# Pi_grammer.net
KiCad netlist of a schematic drawn in EAGLE
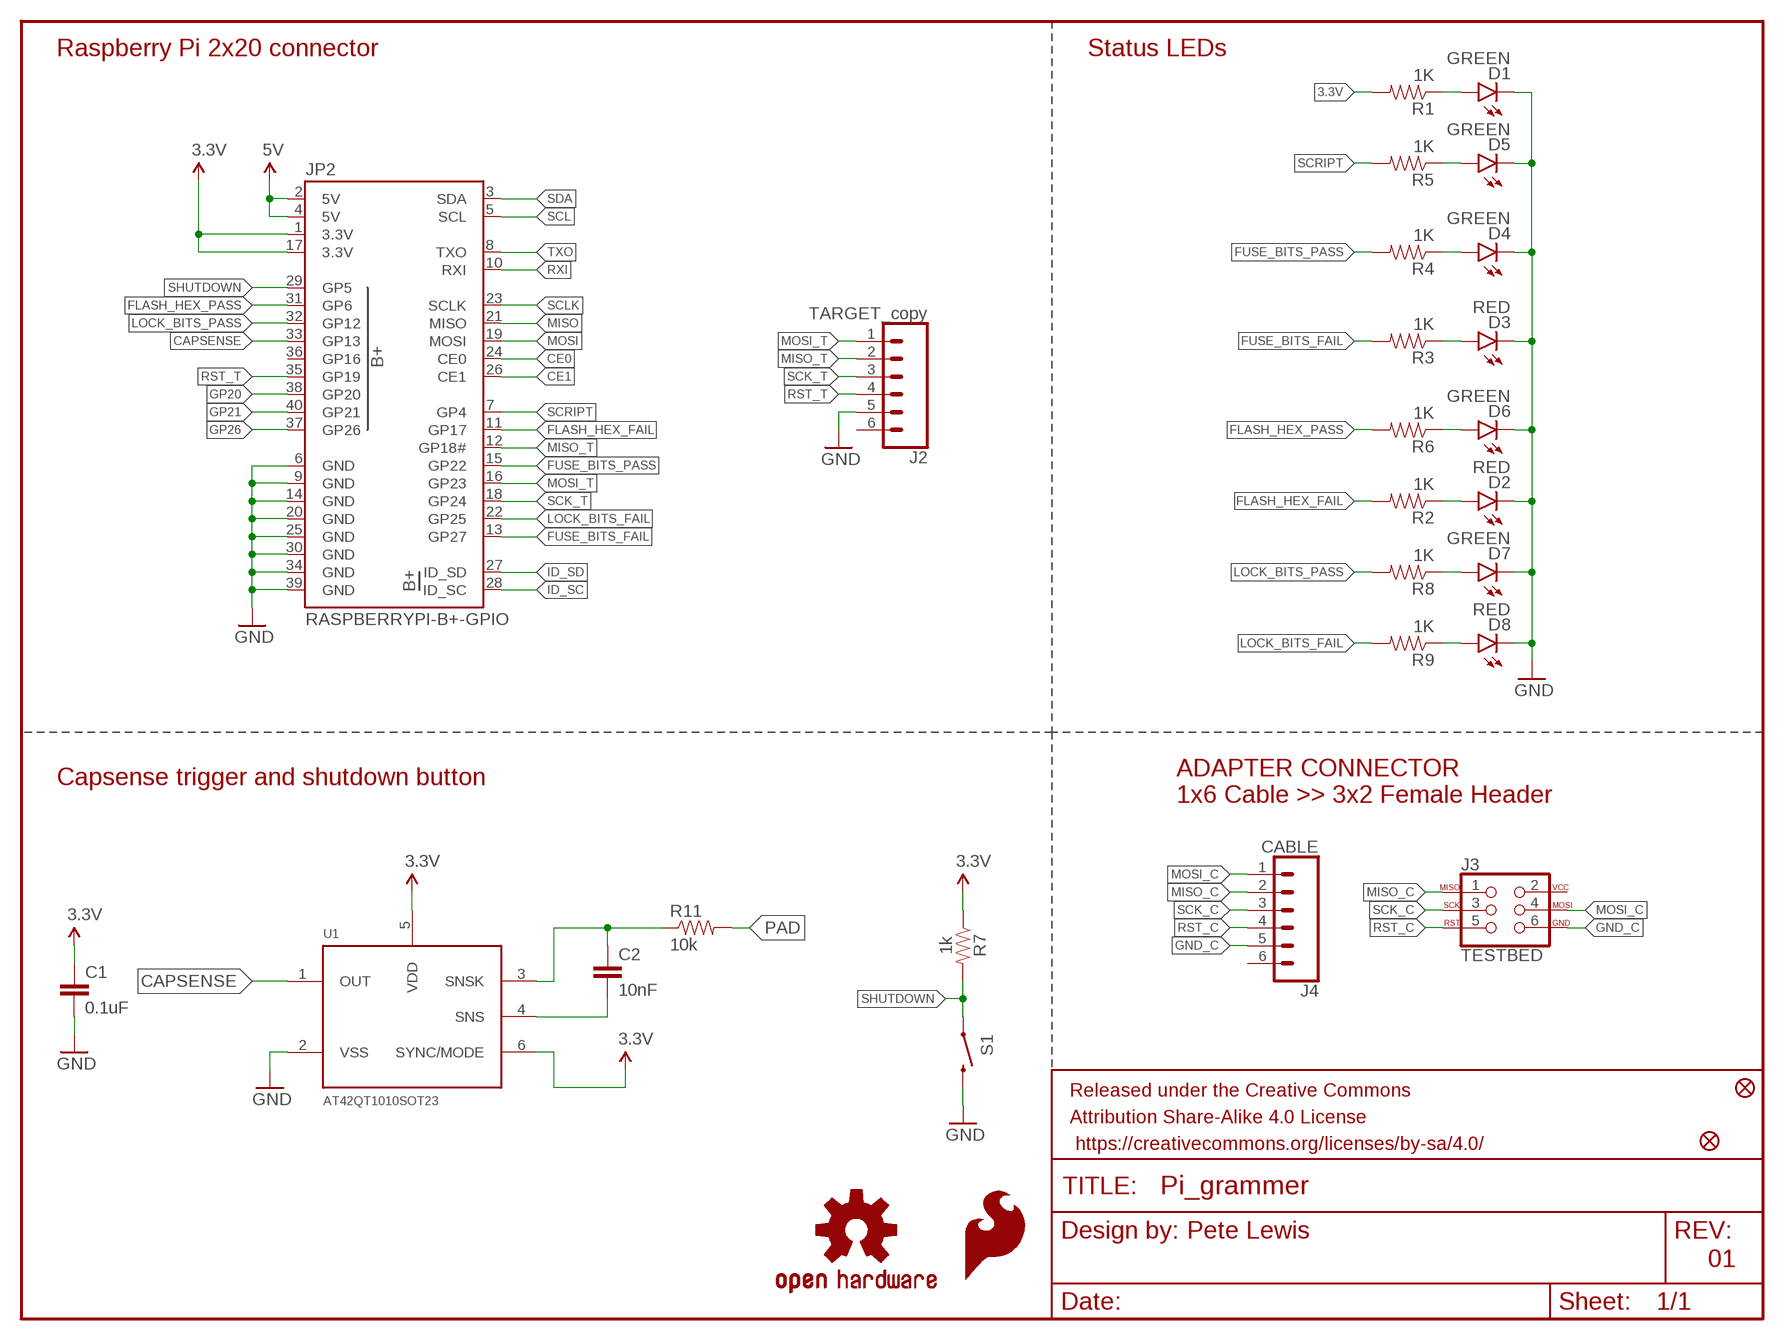
[diagram p0: schematic, sheet 1]

(export (version "E")
  (design (tool "Eeschema 10.0.6"))
  (components
    (comp (ref "C1")
      (value "0.1uF")
      (footprint "eagle-import:0603-CAP")
      (libsource (lib "eagle-import") (part "0.1UF-25V(+80/-20%)(0603)"))
    )
    (comp (ref "C2")
      (value "10nF")
      (footprint "eagle-import:0603-CAP")
      (libsource (lib "eagle-import") (part "10NF/10000PF-50V-10%(0603)"))
    )
    (comp (ref "D1")
      (value "GREEN")
      (footprint "eagle-import:LED-1206")
      (libsource (lib "eagle-import") (part "LED-GREEN1206"))
    )
    (comp (ref "D2")
      (value "RED")
      (footprint "eagle-import:LED-1206")
      (libsource (lib "eagle-import") (part "LED-RED1206"))
    )
    (comp (ref "D3")
      (value "RED")
      (footprint "eagle-import:LED-1206")
      (libsource (lib "eagle-import") (part "LED-RED1206"))
    )
    (comp (ref "D4")
      (value "GREEN")
      (footprint "eagle-import:LED-1206")
      (libsource (lib "eagle-import") (part "LED-GREEN1206"))
    )
    (comp (ref "D5")
      (value "GREEN")
      (footprint "eagle-import:LED-1206")
      (libsource (lib "eagle-import") (part "LED-GREEN1206"))
    )
    (comp (ref "D6")
      (value "GREEN")
      (footprint "eagle-import:LED-1206")
      (libsource (lib "eagle-import") (part "LED-GREEN1206"))
    )
    (comp (ref "D7")
      (value "GREEN")
      (footprint "eagle-import:LED-1206")
      (libsource (lib "eagle-import") (part "LED-GREEN1206"))
    )
    (comp (ref "D8")
      (value "RED")
      (footprint "eagle-import:LED-1206")
      (libsource (lib "eagle-import") (part "LED-RED1206"))
    )
    (comp (ref "FD1")
      (value "FIDUCIALUFIDUCIAL")
      (footprint "eagle-import:FIDUCIAL-MICRO")
      (libsource (lib "eagle-import") (part "FIDUCIALUFIDUCIAL"))
    )
    (comp (ref "FD2")
      (value "FIDUCIALUFIDUCIAL")
      (footprint "eagle-import:FIDUCIAL-MICRO")
      (libsource (lib "eagle-import") (part "FIDUCIALUFIDUCIAL"))
    )
    (comp (ref "FRAME1")
      (value "FRAME-LETTER")
      (footprint "eagle-import:CREATIVE_COMMONS")
      (libsource (lib "eagle-import") (part "FRAME-LETTER"))
    )
    (comp (ref "J2")
      (value "TARGET_copy")
      (footprint "eagle-import:MOLEX-1X6")
      (libsource (lib "eagle-import") (part "CONN_06POLAR"))
    )
    (comp (ref "J3")
      (value "TESTBED")
      (footprint "eagle-import:2X3_LOCK")
      (libsource (lib "eagle-import") (part "AVR_SPI_PROG_3X22X3_LOCK"))
    )
    (comp (ref "J4")
      (value "CABLE")
      (footprint "eagle-import:MOLEX-1X6-RA")
      (libsource (lib "eagle-import") (part "CONN_06RA"))
    )
    (comp (ref "JP2")
      (value "RASPBERRYPI-B+-GPIO")
      (footprint "eagle-import:2X20-SHROUDED")
      (libsource (lib "eagle-import") (part "RASPBERRYPI-B+-GPIO"))
    )
    (comp (ref "LOGO1")
      (value "SFE_LOGO_FLAME.1_INCH")
      (footprint "eagle-import:SFE_LOGO_FLAME_.1")
      (libsource (lib "eagle-import") (part "SFE_LOGO_FLAME.1_INCH"))
    )
    (comp (ref "LOGO2")
      (value "OSHW-LOGOS")
      (footprint "eagle-import:OSHW-LOGO-S")
      (libsource (lib "eagle-import") (part "OSHW-LOGOS"))
    )
    (comp (ref "R1")
      (value "1K")
      (footprint "eagle-import:0603-RES")
      (libsource (lib "eagle-import") (part "1KOHM-1/10W-1%(0603)"))
    )
    (comp (ref "R2")
      (value "1K")
      (footprint "eagle-import:0603-RES")
      (libsource (lib "eagle-import") (part "1KOHM-1/10W-1%(0603)"))
    )
    (comp (ref "R3")
      (value "1K")
      (footprint "eagle-import:0603-RES")
      (libsource (lib "eagle-import") (part "1KOHM-1/10W-1%(0603)"))
    )
    (comp (ref "R4")
      (value "1K")
      (footprint "eagle-import:0603-RES")
      (libsource (lib "eagle-import") (part "1KOHM-1/10W-1%(0603)"))
    )
    (comp (ref "R5")
      (value "1K")
      (footprint "eagle-import:0603-RES")
      (libsource (lib "eagle-import") (part "1KOHM-1/10W-1%(0603)"))
    )
    (comp (ref "R6")
      (value "1K")
      (footprint "eagle-import:0603-RES")
      (libsource (lib "eagle-import") (part "1KOHM-1/10W-1%(0603)"))
    )
    (comp (ref "R7")
      (value "1k")
      (footprint "eagle-import:0603")
      (libsource (lib "eagle-import") (part "1KOHM-0603-1/10W-1%"))
    )
    (comp (ref "R8")
      (value "1K")
      (footprint "eagle-import:0603-RES")
      (libsource (lib "eagle-import") (part "1KOHM-1/10W-1%(0603)"))
    )
    (comp (ref "R9")
      (value "1K")
      (footprint "eagle-import:0603-RES")
      (libsource (lib "eagle-import") (part "1KOHM-1/10W-1%(0603)"))
    )
    (comp (ref "R11")
      (value "10k")
      (footprint "eagle-import:0603-RES")
      (libsource (lib "eagle-import") (part "10KOHM-1/10W-1%(0603)0603"))
    )
    (comp (ref "S1")
      (value "SWITCH-MOMENTARY-2SMD")
      (footprint "eagle-import:TACTILE-SWITCH-SMD")
      (libsource (lib "eagle-import") (part "SWITCH-MOMENTARY-2SMD"))
    )
    (comp (ref "U1")
      (value "AT42QT1010SOT23")
      (footprint "eagle-import:SOT23-6")
      (libsource (lib "eagle-import") (part "AT42QT1010SOT23"))
    )
  )
  (nets
    (net (code "1") (name "3.3V") (class "Default")
      (node (ref "C1") (pin "1") (pinfunction "1_1") (pintype "passive"))
      (node (ref "JP2") (pin "1") (pinfunction "3.3V_1") (pintype "power_in"))
      (node (ref "JP2") (pin "17") (pinfunction "3.3V_17") (pintype "power_in"))
      (node (ref "R1") (pin "2") (pinfunction "2_2") (pintype "passive"))
      (node (ref "R7") (pin "1") (pinfunction "1_1") (pintype "passive"))
      (node (ref "U1") (pin "5") (pinfunction "VDD_5") (pintype "bidirectional"))
      (node (ref "U1") (pin "6") (pinfunction "SYNC/MODE_6") (pintype "bidirectional"))
    )
    (net (code "2") (name "5V") (class "Default")
      (node (ref "JP2") (pin "2") (pinfunction "5V_2") (pintype "power_in"))
      (node (ref "JP2") (pin "4") (pinfunction "5V_4") (pintype "power_in"))
    )
    (net (code "3") (name "CAPSENSE") (class "Default")
      (node (ref "JP2") (pin "33") (pinfunction "GP13_33") (pintype "bidirectional"))
      (node (ref "U1") (pin "1") (pinfunction "OUT_1") (pintype "bidirectional"))
    )
    (net (code "4") (name "CE0") (class "Default")
      (node (ref "JP2") (pin "24") (pinfunction "CE0_24") (pintype "output"))
    )
    (net (code "5") (name "CE1") (class "Default")
      (node (ref "JP2") (pin "26") (pinfunction "CE1_26") (pintype "output"))
    )
    (net (code "6") (name "FLASH_HEX_FAIL") (class "Default")
      (node (ref "JP2") (pin "11") (pinfunction "GP17_11") (pintype "bidirectional"))
      (node (ref "R2") (pin "2") (pinfunction "2_2") (pintype "passive"))
    )
    (net (code "7") (name "FLASH_HEX_PASS") (class "Default")
      (node (ref "JP2") (pin "31") (pinfunction "GP6_31") (pintype "bidirectional"))
      (node (ref "R6") (pin "2") (pinfunction "2_2") (pintype "passive"))
    )
    (net (code "8") (name "FUSE_BITS_FAIL") (class "Default")
      (node (ref "JP2") (pin "13") (pinfunction "GP27_13") (pintype "bidirectional"))
      (node (ref "R3") (pin "2") (pinfunction "2_2") (pintype "passive"))
    )
    (net (code "9") (name "FUSE_BITS_PASS") (class "Default")
      (node (ref "JP2") (pin "15") (pinfunction "GP22_15") (pintype "bidirectional"))
      (node (ref "R4") (pin "2") (pinfunction "2_2") (pintype "passive"))
    )
    (net (code "10") (name "GND") (class "Default")
      (node (ref "C1") (pin "2") (pinfunction "2_2") (pintype "passive"))
      (node (ref "D1") (pin "C") (pinfunction "C_C") (pintype "passive"))
      (node (ref "D2") (pin "C") (pinfunction "C_C") (pintype "passive"))
      (node (ref "D3") (pin "C") (pinfunction "C_C") (pintype "passive"))
      (node (ref "D4") (pin "C") (pinfunction "C_C") (pintype "passive"))
      (node (ref "D5") (pin "C") (pinfunction "C_C") (pintype "passive"))
      (node (ref "D6") (pin "C") (pinfunction "C_C") (pintype "passive"))
      (node (ref "D7") (pin "C") (pinfunction "C_C") (pintype "passive"))
      (node (ref "D8") (pin "C") (pinfunction "C_C") (pintype "passive"))
      (node (ref "J2") (pin "5") (pinfunction "5_5") (pintype "passive"))
      (node (ref "JP2") (pin "14") (pinfunction "GND_14") (pintype "power_in"))
      (node (ref "JP2") (pin "20") (pinfunction "GND_20") (pintype "power_in"))
      (node (ref "JP2") (pin "25") (pinfunction "GND_25") (pintype "power_in"))
      (node (ref "JP2") (pin "30") (pinfunction "GND_30") (pintype "power_in"))
      (node (ref "JP2") (pin "34") (pinfunction "GND_34") (pintype "power_in"))
      (node (ref "JP2") (pin "39") (pinfunction "GND_39") (pintype "power_in"))
      (node (ref "JP2") (pin "6") (pinfunction "GND_6") (pintype "power_in"))
      (node (ref "JP2") (pin "9") (pinfunction "GND_9") (pintype "power_in"))
      (node (ref "S1") (pin "3") (pinfunction "2_3") (pintype "passive"))
      (node (ref "U1") (pin "2") (pinfunction "VSS_2") (pintype "bidirectional"))
    )
    (net (code "11") (name "GND_C") (class "Default")
      (node (ref "J3") (pin "6") (pinfunction "6_6") (pintype "passive"))
      (node (ref "J4") (pin "5") (pinfunction "5_5") (pintype "passive"))
    )
    (net (code "12") (name "GP20") (class "Default")
      (node (ref "JP2") (pin "38") (pinfunction "GP20_38") (pintype "bidirectional"))
    )
    (net (code "13") (name "GP21") (class "Default")
      (node (ref "JP2") (pin "40") (pinfunction "GP21_40") (pintype "bidirectional"))
    )
    (net (code "14") (name "GP26") (class "Default")
      (node (ref "JP2") (pin "37") (pinfunction "GP26_37") (pintype "bidirectional"))
    )
    (net (code "15") (name "ID_SC") (class "Default")
      (node (ref "JP2") (pin "28") (pinfunction "ID_SC_28") (pintype "bidirectional"))
    )
    (net (code "16") (name "ID_SD") (class "Default")
      (node (ref "JP2") (pin "27") (pinfunction "ID_SD_27") (pintype "bidirectional"))
    )
    (net (code "17") (name "LOCK_BITS_FAIL") (class "Default")
      (node (ref "JP2") (pin "22") (pinfunction "GP25_22") (pintype "bidirectional"))
      (node (ref "R9") (pin "2") (pinfunction "2_2") (pintype "passive"))
    )
    (net (code "18") (name "LOCK_BITS_PASS") (class "Default")
      (node (ref "JP2") (pin "32") (pinfunction "GP12_32") (pintype "bidirectional"))
      (node (ref "R8") (pin "2") (pinfunction "2_2") (pintype "passive"))
    )
    (net (code "19") (name "MISO") (class "Default")
      (node (ref "JP2") (pin "21") (pinfunction "MISO_21") (pintype "input"))
    )
    (net (code "20") (name "MISO_C") (class "Default")
      (node (ref "J3") (pin "1") (pinfunction "1_1") (pintype "passive"))
      (node (ref "J4") (pin "2") (pinfunction "2_2") (pintype "passive"))
    )
    (net (code "21") (name "MISO_T") (class "Default")
      (node (ref "J2") (pin "2") (pinfunction "2_2") (pintype "passive"))
      (node (ref "JP2") (pin "12") (pinfunction "GP18#_12") (pintype "bidirectional"))
    )
    (net (code "22") (name "MOSI") (class "Default")
      (node (ref "JP2") (pin "19") (pinfunction "MOSI_19") (pintype "output"))
    )
    (net (code "23") (name "MOSI_C") (class "Default")
      (node (ref "J3") (pin "4") (pinfunction "4_4") (pintype "passive"))
      (node (ref "J4") (pin "1") (pinfunction "1_1") (pintype "passive"))
    )
    (net (code "24") (name "MOSI_T") (class "Default")
      (node (ref "J2") (pin "1") (pinfunction "1_1") (pintype "passive"))
      (node (ref "JP2") (pin "16") (pinfunction "GP23_16") (pintype "bidirectional"))
    )
    (net (code "25") (name "Net-(D1-PadA)") (class "Default")
      (node (ref "D1") (pin "A") (pinfunction "A_A") (pintype "passive"))
      (node (ref "R1") (pin "1") (pinfunction "1_1") (pintype "passive"))
    )
    (net (code "26") (name "Net-(D2-PadA)") (class "Default")
      (node (ref "D2") (pin "A") (pinfunction "A_A") (pintype "passive"))
      (node (ref "R2") (pin "1") (pinfunction "1_1") (pintype "passive"))
    )
    (net (code "27") (name "Net-(D3-PadA)") (class "Default")
      (node (ref "D3") (pin "A") (pinfunction "A_A") (pintype "passive"))
      (node (ref "R3") (pin "1") (pinfunction "1_1") (pintype "passive"))
    )
    (net (code "28") (name "Net-(D4-PadA)") (class "Default")
      (node (ref "D4") (pin "A") (pinfunction "A_A") (pintype "passive"))
      (node (ref "R4") (pin "1") (pinfunction "1_1") (pintype "passive"))
    )
    (net (code "29") (name "Net-(D5-PadA)") (class "Default")
      (node (ref "D5") (pin "A") (pinfunction "A_A") (pintype "passive"))
      (node (ref "R5") (pin "1") (pinfunction "1_1") (pintype "passive"))
    )
    (net (code "30") (name "Net-(D6-PadA)") (class "Default")
      (node (ref "D6") (pin "A") (pinfunction "A_A") (pintype "passive"))
      (node (ref "R6") (pin "1") (pinfunction "1_1") (pintype "passive"))
    )
    (net (code "31") (name "Net-(D7-PadA)") (class "Default")
      (node (ref "D7") (pin "A") (pinfunction "A_A") (pintype "passive"))
      (node (ref "R8") (pin "1") (pinfunction "1_1") (pintype "passive"))
    )
    (net (code "32") (name "Net-(D8-PadA)") (class "Default")
      (node (ref "D8") (pin "A") (pinfunction "A_A") (pintype "passive"))
      (node (ref "R9") (pin "1") (pinfunction "1_1") (pintype "passive"))
    )
    (net (code "33") (name "Net-(U1-SNS)") (class "Default")
      (node (ref "C2") (pin "2") (pinfunction "2_2") (pintype "passive"))
      (node (ref "U1") (pin "4") (pinfunction "SNS_4") (pintype "bidirectional"))
    )
    (net (code "34") (name "Net-(U1-SNSK)") (class "Default")
      (node (ref "C2") (pin "1") (pinfunction "1_1") (pintype "passive"))
      (node (ref "R11") (pin "1") (pinfunction "1_1") (pintype "passive"))
      (node (ref "U1") (pin "3") (pinfunction "SNSK_3") (pintype "bidirectional"))
    )
    (net (code "35") (name "PAD") (class "Default")
      (node (ref "R11") (pin "2") (pinfunction "2_2") (pintype "passive"))
    )
    (net (code "36") (name "RST_C") (class "Default")
      (node (ref "J3") (pin "5") (pinfunction "5_5") (pintype "passive"))
      (node (ref "J4") (pin "4") (pinfunction "4_4") (pintype "passive"))
    )
    (net (code "37") (name "RST_T") (class "Default")
      (node (ref "J2") (pin "4") (pinfunction "4_4") (pintype "passive"))
      (node (ref "JP2") (pin "35") (pinfunction "GP19_35") (pintype "bidirectional"))
    )
    (net (code "38") (name "RXI") (class "Default")
      (node (ref "JP2") (pin "10") (pinfunction "RXI_10") (pintype "input"))
    )
    (net (code "39") (name "SCK_C") (class "Default")
      (node (ref "J3") (pin "3") (pinfunction "3_3") (pintype "passive"))
      (node (ref "J4") (pin "3") (pinfunction "3_3") (pintype "passive"))
    )
    (net (code "40") (name "SCK_T") (class "Default")
      (node (ref "J2") (pin "3") (pinfunction "3_3") (pintype "passive"))
      (node (ref "JP2") (pin "18") (pinfunction "GP24_18") (pintype "bidirectional"))
    )
    (net (code "41") (name "SCL") (class "Default")
      (node (ref "JP2") (pin "5") (pinfunction "SCL_5") (pintype "bidirectional"))
    )
    (net (code "42") (name "SCLK") (class "Default")
      (node (ref "JP2") (pin "23") (pinfunction "SCLK_23") (pintype "output"))
    )
    (net (code "43") (name "SCRIPT") (class "Default")
      (node (ref "JP2") (pin "7") (pinfunction "GP4_7") (pintype "bidirectional"))
      (node (ref "R5") (pin "2") (pinfunction "2_2") (pintype "passive"))
    )
    (net (code "44") (name "SDA") (class "Default")
      (node (ref "JP2") (pin "3") (pinfunction "SDA_3") (pintype "bidirectional"))
    )
    (net (code "45") (name "SHUTDOWN") (class "Default")
      (node (ref "JP2") (pin "29") (pinfunction "GP5_29") (pintype "bidirectional"))
      (node (ref "R7") (pin "2") (pinfunction "2_2") (pintype "passive"))
      (node (ref "S1") (pin "1") (pinfunction "1_1") (pintype "passive"))
    )
    (net (code "46") (name "TXO") (class "Default")
      (node (ref "JP2") (pin "8") (pinfunction "TXO_8") (pintype "output"))
    )
    (net (code "47") (name "unconnected-(J2-Pad6)") (class "Default")
      (node (ref "J2") (pin "6") (pinfunction "6_6") (pintype "passive"))
    )
    (net (code "48") (name "unconnected-(J3-Pad2)") (class "Default")
      (node (ref "J3") (pin "2") (pinfunction "2_2") (pintype "passive"))
    )
    (net (code "49") (name "unconnected-(J4-Pad6)") (class "Default")
      (node (ref "J4") (pin "6") (pinfunction "6_6") (pintype "passive"))
    )
    (net (code "50") (name "unconnected-(JP2-GP16-Pad36)") (class "Default")
      (node (ref "JP2") (pin "36") (pinfunction "GP16_36") (pintype "bidirectional"))
    )
  )
)
